# RPI_3.net
KiCad netlist of a schematic drawn in Altium Designer
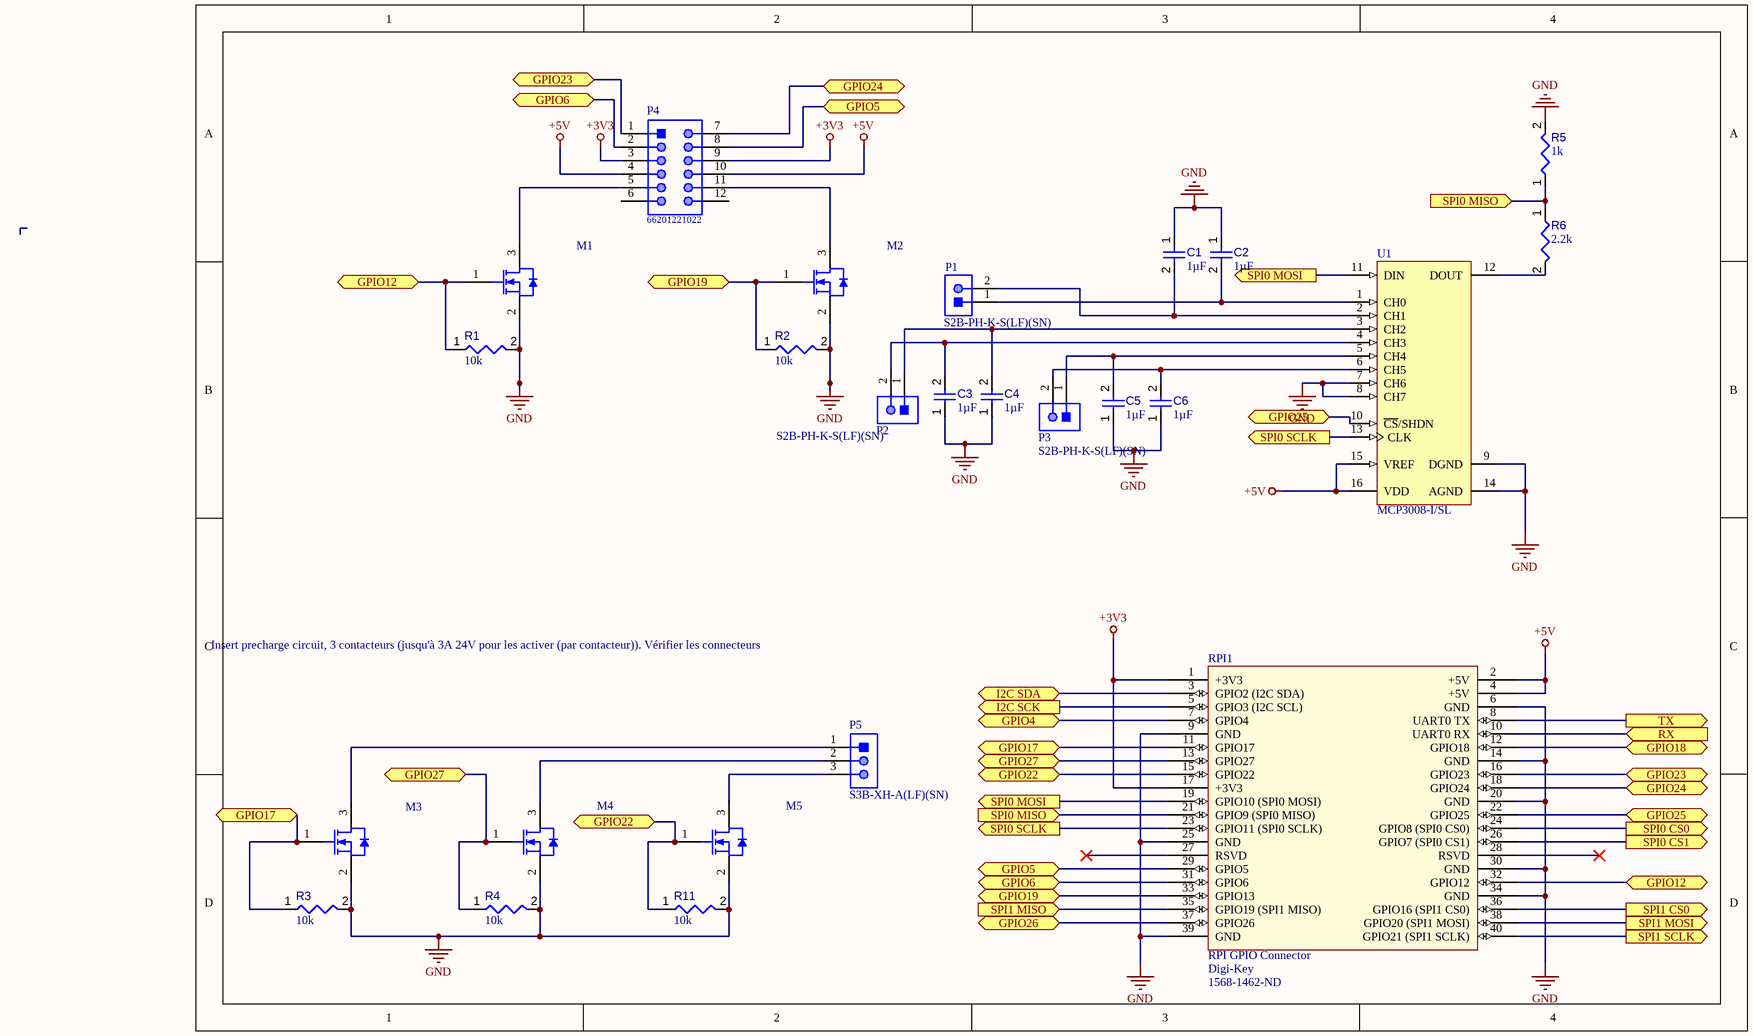
[diagram p0: RPI 3.SchDoc]

(export (version "E")
  (design (tool "Eeschema 10.0.6"))
  (components
    (comp (ref "C1")
      (value "1µF")
      (footprint "CAPC1005X55X25ML5T10")
      (description "Chip Capacitor, 1 uF, +/- 10%, 6.3 V, 1005 (0402 Metric)")
      (fields (field (name "TOLERANCE") "10%") (field (name "Comment") "Capacitor 1 uF +/- 10% 6.3 V 1005"))
      (libsource (lib "École Polytechnique de Montréal") (part "CAP-NP-2"))
    )
    (comp (ref "C2")
      (value "1µF")
      (footprint "CAPC1005X55X25ML5T10")
      (description "Chip Capacitor, 1 uF, +/- 10%, 6.3 V, 1005 (0402 Metric)")
      (fields (field (name "TOLERANCE") "10%") (field (name "Comment") "Capacitor 1 uF +/- 10% 6.3 V 1005"))
      (libsource (lib "École Polytechnique de Montréal") (part "CAP-NP-2"))
    )
    (comp (ref "C3")
      (value "1µF")
      (footprint "CAPC1005X55X25ML5T10")
      (description "Chip Capacitor, 1 uF, +/- 10%, 6.3 V, 1005 (0402 Metric)")
      (fields (field (name "TOLERANCE") "10%") (field (name "Comment") "Capacitor 1 uF +/- 10% 6.3 V 1005"))
      (libsource (lib "École Polytechnique de Montréal") (part "CAP-NP-2"))
    )
    (comp (ref "C4")
      (value "1µF")
      (footprint "CAPC1005X55X25ML5T10")
      (description "Chip Capacitor, 1 uF, +/- 10%, 6.3 V, 1005 (0402 Metric)")
      (fields (field (name "TOLERANCE") "10%") (field (name "Comment") "Capacitor 1 uF +/- 10% 6.3 V 1005"))
      (libsource (lib "École Polytechnique de Montréal") (part "CAP-NP-2"))
    )
    (comp (ref "C5")
      (value "1µF")
      (footprint "CAPC1005X55X25ML5T10")
      (description "Chip Capacitor, 1 uF, +/- 10%, 6.3 V, 1005 (0402 Metric)")
      (fields (field (name "TOLERANCE") "10%") (field (name "Comment") "Capacitor 1 uF +/- 10% 6.3 V 1005"))
      (libsource (lib "École Polytechnique de Montréal") (part "CAP-NP-2"))
    )
    (comp (ref "C6")
      (value "1µF")
      (footprint "CAPC1005X55X25ML5T10")
      (description "Chip Capacitor, 1 uF, +/- 10%, 6.3 V, 1005 (0402 Metric)")
      (fields (field (name "TOLERANCE") "10%") (field (name "Comment") "Capacitor 1 uF +/- 10% 6.3 V 1005"))
      (libsource (lib "École Polytechnique de Montréal") (part "CAP-NP-2"))
    )
    (comp (ref "M1")
      (value "BSS138")
      (footprint "FAIR-SOT23-3_V")
      (fields (field (name "MANUFACTURER") "Fairchild") (field (name "POWER") "360mW"))
      (libsource (lib "École Polytechnique de Montréal") (part "NEMOS-GSD-3"))
    )
    (comp (ref "M2")
      (value "BSS138")
      (footprint "FAIR-SOT23-3_V")
      (fields (field (name "MANUFACTURER") "Fairchild") (field (name "POWER") "360mW"))
      (libsource (lib "École Polytechnique de Montréal") (part "NEMOS-GSD-3"))
    )
    (comp (ref "M3")
      (value "BSS138")
      (footprint "FAIR-SOT23-3_V")
      (fields (field (name "MANUFACTURER") "Fairchild") (field (name "POWER") "360mW"))
      (libsource (lib "École Polytechnique de Montréal") (part "NEMOS-GSD-3"))
    )
    (comp (ref "M4")
      (value "BSS138")
      (footprint "FAIR-SOT23-3_V")
      (fields (field (name "MANUFACTURER") "Fairchild") (field (name "POWER") "360mW"))
      (libsource (lib "École Polytechnique de Montréal") (part "NEMOS-GSD-3"))
    )
    (comp (ref "M5")
      (value "BSS138")
      (footprint "FAIR-SOT23-3_V")
      (fields (field (name "MANUFACTURER") "Fairchild") (field (name "POWER") "360mW"))
      (libsource (lib "École Polytechnique de Montréal") (part "NEMOS-GSD-3"))
    )
    (comp (ref "P1")
      (value "S2B-PH-K-S(LF)(SN)")
      (footprint "JST-S2B-PH-K-S_V")
      (fields (field (name "MANUFACTURER") "Japan Solderless Terminals"))
      (libsource (lib "") (part "CN-1P-M-R2_1"))
    )
    (comp (ref "P2")
      (value "S2B-PH-K-S(LF)(SN)")
      (footprint "JST-S2B-PH-K-S_V")
      (fields (field (name "MANUFACTURER") "Japan Solderless Terminals"))
      (libsource (lib "École Polytechnique de Montréal") (part "CN-1P-M-R2"))
    )
    (comp (ref "P3")
      (value "S2B-PH-K-S(LF)(SN)")
      (footprint "JST-S2B-PH-K-S_V")
      (fields (field (name "MANUFACTURER") "Japan Solderless Terminals"))
      (libsource (lib "École Polytechnique de Montréal") (part "CN-1P-M-R2"))
    )
    (comp (ref "P4")
      (value "66201221022")
      (footprint "66201221022")
      (description "THT Male Header WR-MPC3, with Snap-in Plastic Pegs, Right Angled, Dual Row, pitch 3 mm, 12 pins")
      (libsource (lib "École Polytechnique de Montréal") (part "WE-CN-2P-M-R12_A"))
    )
    (comp (ref "P5")
      (value "S3B-XH-A(LF)(SN)")
      (footprint "JST-S3B-XH-A(LF)(SN)_V")
      (fields (field (name "MANUFACTURER") "JST"))
      (libsource (lib "École Polytechnique de Montréal") (part "CN-1P-M-R3"))
    )
    (comp (ref "R1")
      (value "10k")
      (footprint "RESC0402(1005)_L")
      (description "Chip Resistor, 10 kOhms, +/-1 %, 63 mW, -55 to 125 degC, 0402")
      (fields (field (name "POWER") "63mW") (field (name "TOLERANCE") "1%"))
      (libsource (lib "École Polytechnique de Montréal") (part "RES-2"))
    )
    (comp (ref "R2")
      (value "10k")
      (footprint "RESC0402(1005)_L")
      (description "Chip Resistor, 10 kOhms, +/-1 %, 63 mW, -55 to 125 degC, 0402")
      (fields (field (name "POWER") "63mW") (field (name "TOLERANCE") "1%"))
      (libsource (lib "École Polytechnique de Montréal") (part "RES-2"))
    )
    (comp (ref "R3")
      (value "10k")
      (footprint "RESC0402(1005)_L")
      (description "Chip Resistor, 10 kOhms, +/-1 %, 63 mW, -55 to 125 degC, 0402")
      (fields (field (name "POWER") "63mW") (field (name "TOLERANCE") "1%"))
      (libsource (lib "École Polytechnique de Montréal") (part "RES-2"))
    )
    (comp (ref "R4")
      (value "10k")
      (footprint "RESC0402(1005)_L")
      (description "Chip Resistor, 10 kOhms, +/-1 %, 63 mW, -55 to 125 degC, 0402")
      (fields (field (name "POWER") "63mW") (field (name "TOLERANCE") "1%"))
      (libsource (lib "École Polytechnique de Montréal") (part "RES-2"))
    )
    (comp (ref "R5")
      (value "1k")
      (footprint "RESC1005X40X25ML10T10")
      (description "Chip Resistor, 1 KOhm, +/- 5%, 0.063 W, -55 to 155 degC, 0402 (1005 Metric)")
      (fields (field (name "TOLERANCE") "5%") (field (name "POWER") "63mW"))
      (libsource (lib "École Polytechnique de Montréal") (part "RES-2"))
    )
    (comp (ref "R6")
      (value "2.2k")
      (footprint "RESC0402(1005)_L")
      (description "Chip Resistor, 2,2 kOhms, +/-5 %, 63 mW, -55 to 155 degC, 0402")
      (fields (field (name "POWER") "63mW") (field (name "TOLERANCE") "5%"))
      (libsource (lib "École Polytechnique de Montréal") (part "RES-2"))
    )
    (comp (ref "R11")
      (value "10k")
      (footprint "RESC0402(1005)_L")
      (description "Chip Resistor, 10 kOhms, +/-1 %, 63 mW, -55 to 125 degC, 0402")
      (fields (field (name "POWER") "63mW") (field (name "TOLERANCE") "1%"))
      (libsource (lib "École Polytechnique de Montréal") (part "RES-2"))
    )
    (comp (ref "RPI1")
      (value "RPI GPIO Connector")
      (footprint "rpi")
      (description "GPIO Header for Raspberry Pi A+/B+/Pi 2/Pi 3 - 2x20")
      (fields
        (field (name "MANUFACTURER") "SparkFun Electronics")
        (field (name "MANUFACTURER PART NUMBER") "PRT-14017")
        (field (name "SUPPLIER 1") "Digi-Key")
        (field (name "SUPPLIER PART NUMBER 1") "1568-1462-ND")
      )
      (libsource (lib "rpi") (part "rpi connector"))
    )
    (comp (ref "U1")
      (value "MCP3008-I/SL")
      (footprint "SOIC-SL16_L")
      (libsource (lib "Altium Content Vault") (part "CON-ADC-MCP3008-16"))
    )
  )
  (nets
    (net (code "1") (name "+3V3") (class "Default")
      (node (ref "P4") (pin "3") (pinfunction "3_3") (pintype "passive"))
      (node (ref "P4") (pin "9") (pinfunction "9_9") (pintype "passive"))
      (node (ref "RPI1") (pin "1") (pinfunction "+3V3_1") (pintype "power_in"))
      (node (ref "RPI1") (pin "17") (pinfunction "+3V3_17") (pintype "power_in"))
    )
    (net (code "2") (name "+5V") (class "Default")
      (node (ref "P4") (pin "10") (pinfunction "10_10") (pintype "passive"))
      (node (ref "P4") (pin "4") (pinfunction "4_4") (pintype "passive"))
      (node (ref "RPI1") (pin "2") (pinfunction "+5V_2") (pintype "power_in"))
      (node (ref "RPI1") (pin "4") (pinfunction "+5V_4") (pintype "power_in"))
      (node (ref "U1") (pin "15") (pinfunction "VREF_15") (pintype "input"))
      (node (ref "U1") (pin "16") (pinfunction "VDD_16") (pintype "power_in"))
    )
    (net (code "3") (name "/GPIO4") (class "Default")
      (node (ref "RPI1") (pin "7") (pinfunction "GPIO4_7") (pintype "bidirectional"))
    )
    (net (code "4") (name "/GPIO5") (class "Default")
      (node (ref "P4") (pin "8") (pinfunction "8_8") (pintype "passive"))
      (node (ref "RPI1") (pin "29") (pinfunction "GPIO5_29") (pintype "bidirectional"))
    )
    (net (code "5") (name "/GPIO6") (class "Default")
      (node (ref "P4") (pin "2") (pinfunction "2_2") (pintype "passive"))
      (node (ref "RPI1") (pin "31") (pinfunction "GPIO6_31") (pintype "bidirectional"))
    )
    (net (code "6") (name "/GPIO12") (class "Default")
      (node (ref "M1") (pin "1") (pinfunction "G_1") (pintype "passive"))
      (node (ref "R1") (pin "1") (pinfunction "1_1") (pintype "passive"))
      (node (ref "RPI1") (pin "32") (pinfunction "GPIO12_32") (pintype "bidirectional"))
    )
    (net (code "7") (name "/GPIO17") (class "Default")
      (node (ref "M3") (pin "1") (pinfunction "G_1") (pintype "passive"))
      (node (ref "R3") (pin "1") (pinfunction "1_1") (pintype "passive"))
      (node (ref "RPI1") (pin "11") (pinfunction "GPIO17_11") (pintype "bidirectional"))
    )
    (net (code "8") (name "/GPIO18") (class "Default")
      (node (ref "RPI1") (pin "12") (pinfunction "GPIO18_12") (pintype "bidirectional"))
    )
    (net (code "9") (name "/GPIO19") (class "Default")
      (node (ref "M2") (pin "1") (pinfunction "G_1") (pintype "passive"))
      (node (ref "R2") (pin "1") (pinfunction "1_1") (pintype "passive"))
      (node (ref "RPI1") (pin "33") (pinfunction "GPIO13_33") (pintype "bidirectional"))
    )
    (net (code "10") (name "/GPIO22") (class "Default")
      (node (ref "M5") (pin "1") (pinfunction "G_1") (pintype "passive"))
      (node (ref "R11") (pin "1") (pinfunction "1_1") (pintype "passive"))
      (node (ref "RPI1") (pin "15") (pinfunction "GPIO22_15") (pintype "bidirectional"))
    )
    (net (code "11") (name "/GPIO23") (class "Default")
      (node (ref "P4") (pin "1") (pinfunction "1_1") (pintype "passive"))
      (node (ref "RPI1") (pin "16") (pinfunction "GPIO23_16") (pintype "bidirectional"))
    )
    (net (code "12") (name "/GPIO24") (class "Default")
      (node (ref "P4") (pin "7") (pinfunction "7_7") (pintype "passive"))
      (node (ref "RPI1") (pin "18") (pinfunction "GPIO24_18") (pintype "bidirectional"))
    )
    (net (code "13") (name "/GPIO25") (class "Default")
      (node (ref "RPI1") (pin "22") (pinfunction "GPIO25_22") (pintype "bidirectional"))
      (node (ref "U1") (pin "10") (pinfunction "~{CS}/SHDN_10") (pintype "input"))
    )
    (net (code "14") (name "/GPIO26") (class "Default")
      (node (ref "RPI1") (pin "37") (pinfunction "GPIO26_37") (pintype "bidirectional"))
    )
    (net (code "15") (name "/GPIO27") (class "Default")
      (node (ref "M4") (pin "1") (pinfunction "G_1") (pintype "passive"))
      (node (ref "R4") (pin "1") (pinfunction "1_1") (pintype "passive"))
      (node (ref "RPI1") (pin "13") (pinfunction "GPIO27_13") (pintype "bidirectional"))
    )
    (net (code "16") (name "/I2C SCK") (class "Default")
      (node (ref "RPI1") (pin "5") (pinfunction "GPIO3_(I2C_SCL)_5") (pintype "bidirectional"))
    )
    (net (code "17") (name "/I2C SDA") (class "Default")
      (node (ref "RPI1") (pin "3") (pinfunction "GPIO2_(I2C_SDA)_3") (pintype "bidirectional"))
    )
    (net (code "18") (name "/RX") (class "Default")
      (node (ref "RPI1") (pin "10") (pinfunction "UART0_RX_10") (pintype "bidirectional"))
    )
    (net (code "19") (name "/SPI0 CS0") (class "Default")
      (node (ref "RPI1") (pin "24") (pinfunction "GPIO8_(SPI0_CS0)_24") (pintype "bidirectional"))
    )
    (net (code "20") (name "/SPI0 CS1") (class "Default")
      (node (ref "RPI1") (pin "26") (pinfunction "GPIO7_(SPI0_CS1)_26") (pintype "bidirectional"))
    )
    (net (code "21") (name "/SPI0 MISO") (class "Default")
      (node (ref "R5") (pin "1") (pinfunction "1_1") (pintype "passive"))
      (node (ref "R6") (pin "1") (pinfunction "1_1") (pintype "passive"))
      (node (ref "RPI1") (pin "21") (pinfunction "GPIO9_(SPI0_MISO)_21") (pintype "bidirectional"))
    )
    (net (code "22") (name "/SPI0 MOSI") (class "Default")
      (node (ref "RPI1") (pin "19") (pinfunction "GPIO10_(SPI0_MOSI)_19") (pintype "bidirectional"))
      (node (ref "U1") (pin "11") (pinfunction "DIN_11") (pintype "input"))
    )
    (net (code "23") (name "/SPI0 SCLK") (class "Default")
      (node (ref "RPI1") (pin "23") (pinfunction "GPIO11_(SPI0_SCLK)_23") (pintype "bidirectional"))
      (node (ref "U1") (pin "13") (pinfunction "CLK_13") (pintype "input"))
    )
    (net (code "24") (name "/SPI1 CS0") (class "Default")
      (node (ref "RPI1") (pin "36") (pinfunction "GPIO16_(SPI1_CS0)_36") (pintype "bidirectional"))
    )
    (net (code "25") (name "/SPI1 MISO") (class "Default")
      (node (ref "RPI1") (pin "35") (pinfunction "GPIO19_(SPI1_MISO)_35") (pintype "bidirectional"))
    )
    (net (code "26") (name "/SPI1 MOSI") (class "Default")
      (node (ref "RPI1") (pin "38") (pinfunction "GPIO20_(SPI1_MOSI)_38") (pintype "bidirectional"))
    )
    (net (code "27") (name "/SPI1 SCLK") (class "Default")
      (node (ref "RPI1") (pin "40") (pinfunction "GPIO21_(SPI1_SCLK)_40") (pintype "bidirectional"))
    )
    (net (code "28") (name "/TX") (class "Default")
      (node (ref "RPI1") (pin "8") (pinfunction "UART0_TX_8") (pintype "bidirectional"))
    )
    (net (code "29") (name "GND") (class "Default")
      (node (ref "C1") (pin "1") (pinfunction "1_1") (pintype "passive"))
      (node (ref "C2") (pin "1") (pinfunction "1_1") (pintype "passive"))
      (node (ref "C3") (pin "1") (pinfunction "1_1") (pintype "passive"))
      (node (ref "C4") (pin "1") (pinfunction "1_1") (pintype "passive"))
      (node (ref "C5") (pin "1") (pinfunction "1_1") (pintype "passive"))
      (node (ref "C6") (pin "1") (pinfunction "1_1") (pintype "passive"))
      (node (ref "M1") (pin "2") (pinfunction "S_2") (pintype "passive"))
      (node (ref "M2") (pin "2") (pinfunction "S_2") (pintype "passive"))
      (node (ref "M3") (pin "2") (pinfunction "S_2") (pintype "passive"))
      (node (ref "M4") (pin "2") (pinfunction "S_2") (pintype "passive"))
      (node (ref "M5") (pin "2") (pinfunction "S_2") (pintype "passive"))
      (node (ref "R1") (pin "2") (pinfunction "2_2") (pintype "passive"))
      (node (ref "R11") (pin "2") (pinfunction "2_2") (pintype "passive"))
      (node (ref "R2") (pin "2") (pinfunction "2_2") (pintype "passive"))
      (node (ref "R3") (pin "2") (pinfunction "2_2") (pintype "passive"))
      (node (ref "R4") (pin "2") (pinfunction "2_2") (pintype "passive"))
      (node (ref "R5") (pin "2") (pinfunction "2_2") (pintype "passive"))
      (node (ref "RPI1") (pin "14") (pinfunction "GND_14") (pintype "power_in"))
      (node (ref "RPI1") (pin "20") (pinfunction "GND_20") (pintype "power_in"))
      (node (ref "RPI1") (pin "25") (pinfunction "GND_25") (pintype "power_in"))
      (node (ref "RPI1") (pin "30") (pinfunction "GND_30") (pintype "power_in"))
      (node (ref "RPI1") (pin "34") (pinfunction "GND_34") (pintype "passive"))
      (node (ref "RPI1") (pin "39") (pinfunction "GND_39") (pintype "power_in"))
      (node (ref "RPI1") (pin "6") (pinfunction "GND_6") (pintype "power_in"))
      (node (ref "RPI1") (pin "9") (pinfunction "GND_9") (pintype "power_in"))
      (node (ref "U1") (pin "14") (pinfunction "AGND_14") (pintype "power_in"))
      (node (ref "U1") (pin "7") (pinfunction "CH6_7") (pintype "input"))
      (node (ref "U1") (pin "8") (pinfunction "CH7_8") (pintype "input"))
      (node (ref "U1") (pin "9") (pinfunction "DGND_9") (pintype "power_in"))
    )
    (net (code "30") (name "Net-(M1-D)") (class "Default")
      (node (ref "M1") (pin "3") (pinfunction "D_3") (pintype "passive"))
      (node (ref "P4") (pin "5") (pinfunction "5_5") (pintype "passive"))
    )
    (net (code "31") (name "Net-(M2-D)") (class "Default")
      (node (ref "M2") (pin "3") (pinfunction "D_3") (pintype "passive"))
      (node (ref "P4") (pin "11") (pinfunction "11_11") (pintype "passive"))
    )
    (net (code "32") (name "Net-(M3-D)") (class "Default")
      (node (ref "M3") (pin "3") (pinfunction "D_3") (pintype "passive"))
      (node (ref "P5") (pin "1") (pinfunction "1_1") (pintype "passive"))
    )
    (net (code "33") (name "Net-(M4-D)") (class "Default")
      (node (ref "M4") (pin "3") (pinfunction "D_3") (pintype "passive"))
      (node (ref "P5") (pin "2") (pinfunction "2_2") (pintype "passive"))
    )
    (net (code "34") (name "Net-(M5-D)") (class "Default")
      (node (ref "M5") (pin "3") (pinfunction "D_3") (pintype "passive"))
      (node (ref "P5") (pin "3") (pinfunction "3_3") (pintype "passive"))
    )
    (net (code "35") (name "Net-(U1-CH0)") (class "Default")
      (node (ref "C2") (pin "2") (pinfunction "2_2") (pintype "passive"))
      (node (ref "P1") (pin "1") (pinfunction "1_1") (pintype "passive"))
      (node (ref "U1") (pin "1") (pinfunction "CH0_1") (pintype "input"))
    )
    (net (code "36") (name "Net-(U1-CH1)") (class "Default")
      (node (ref "C1") (pin "2") (pinfunction "2_2") (pintype "passive"))
      (node (ref "P1") (pin "2") (pinfunction "2_2") (pintype "passive"))
      (node (ref "U1") (pin "2") (pinfunction "CH1_2") (pintype "input"))
    )
    (net (code "37") (name "Net-(U1-CH2)") (class "Default")
      (node (ref "C4") (pin "2") (pinfunction "2_2") (pintype "passive"))
      (node (ref "P2") (pin "1") (pinfunction "1_1") (pintype "passive"))
      (node (ref "U1") (pin "3") (pinfunction "CH2_3") (pintype "input"))
    )
    (net (code "38") (name "Net-(U1-CH3)") (class "Default")
      (node (ref "C3") (pin "2") (pinfunction "2_2") (pintype "passive"))
      (node (ref "P2") (pin "2") (pinfunction "2_2") (pintype "passive"))
      (node (ref "U1") (pin "4") (pinfunction "CH3_4") (pintype "input"))
    )
    (net (code "39") (name "Net-(U1-CH4)") (class "Default")
      (node (ref "C5") (pin "2") (pinfunction "2_2") (pintype "passive"))
      (node (ref "P3") (pin "1") (pinfunction "1_1") (pintype "passive"))
      (node (ref "U1") (pin "5") (pinfunction "CH4_5") (pintype "input"))
    )
    (net (code "40") (name "Net-(U1-CH5)") (class "Default")
      (node (ref "C6") (pin "2") (pinfunction "2_2") (pintype "passive"))
      (node (ref "P3") (pin "2") (pinfunction "2_2") (pintype "passive"))
      (node (ref "U1") (pin "6") (pinfunction "CH5_6") (pintype "input"))
    )
    (net (code "41") (name "Net-(U1-DOUT)") (class "Default")
      (node (ref "R6") (pin "2") (pinfunction "2_2") (pintype "passive"))
      (node (ref "U1") (pin "12") (pinfunction "DOUT_12") (pintype "tri_state"))
    )
    (net (code "42") (name "unconnected-(P4-Pad6)") (class "Default")
      (node (ref "P4") (pin "6") (pinfunction "6_6") (pintype "passive"))
    )
    (net (code "43") (name "unconnected-(P4-Pad12)") (class "Default")
      (node (ref "P4") (pin "12") (pinfunction "12_12") (pintype "passive"))
    )
    (net (code "44") (name "unconnected-(RPI1-RSVD-Pad27)") (class "Default")
      (node (ref "RPI1") (pin "27") (pinfunction "RSVD_27") (pintype "passive+no_connect"))
    )
    (net (code "45") (name "unconnected-(RPI1-RSVD-Pad28)") (class "Default")
      (node (ref "RPI1") (pin "28") (pinfunction "RSVD_28") (pintype "passive+no_connect"))
    )
  )
)
